# gateway_nano.net
KiCad netlist of a schematic drawn in EAGLE
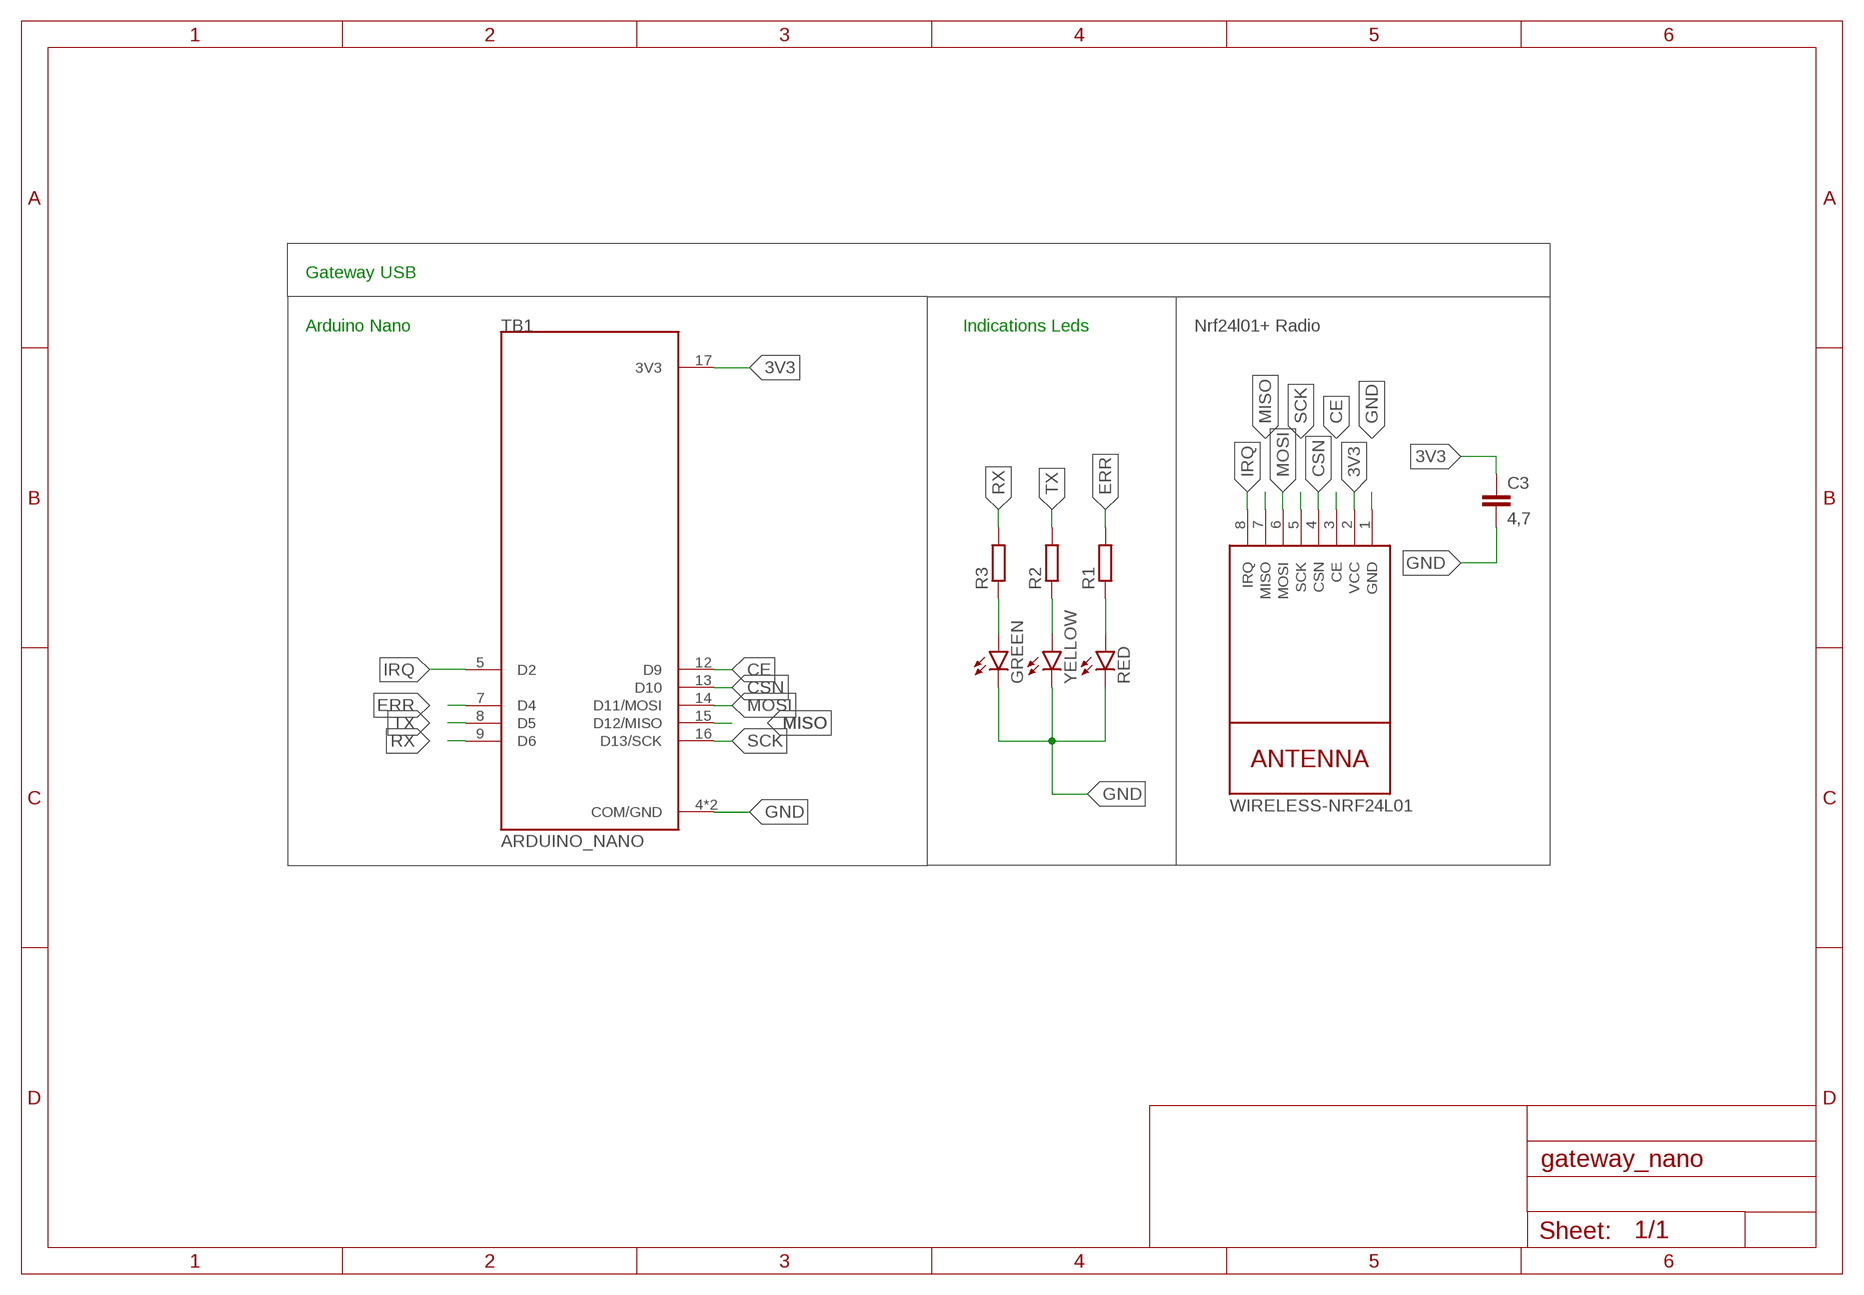
[diagram p0: schematic, sheet 1]

(export (version "E")
  (design (tool "Eeschema 10.0.6"))
  (components
    (comp (ref "C3")
      (value "4,7")
      (footprint "eagle-import:C2.5-2")
      (libsource (lib "eagle-import") (part "C2.5/2"))
    )
    (comp (ref "GREEN")
      (value "LED5MM")
      (footprint "eagle-import:LED5MM")
      (libsource (lib "eagle-import") (part "LED5MM"))
    )
    (comp (ref "NRF24L01+")
      (value "WIRELESS-NRF24L01")
      (footprint "eagle-import:WIRELESS-NRF24L01")
      (libsource (lib "eagle-import") (part "WIRELESS-NRF24L01"))
    )
    (comp (ref "R1")
      (value "R-EU_R0805")
      (footprint "eagle-import:R0805")
      (libsource (lib "eagle-import") (part "R-EU_R0805"))
    )
    (comp (ref "R2")
      (value "R-EU_R0805")
      (footprint "eagle-import:R0805")
      (libsource (lib "eagle-import") (part "R-EU_R0805"))
    )
    (comp (ref "R3")
      (value "R-EU_R0805")
      (footprint "eagle-import:R0805")
      (libsource (lib "eagle-import") (part "R-EU_R0805"))
    )
    (comp (ref "RED")
      (value "LED5MM")
      (footprint "eagle-import:LED5MM")
      (libsource (lib "eagle-import") (part "LED5MM"))
    )
    (comp (ref "TB1")
      (value "ARDUINO_NANO")
      (footprint "eagle-import:SHIELD_ARDUINO_NANO")
      (fields (field (name "MF") "Arduino") (field (name "MP") "ARDUINO NANO"))
      (libsource (lib "eagle-import") (part "ARDUINO_NANO"))
    )
    (comp (ref "YELLOW")
      (value "LED5MM")
      (footprint "eagle-import:LED5MM")
      (libsource (lib "eagle-import") (part "LED5MM"))
    )
  )
  (nets
    (net (code "1") (name "3V3") (class "Default")
      (node (ref "C3") (pin "1") (pinfunction "1_1") (pintype "passive"))
      (node (ref "NRF24L01+") (pin "2") (pinfunction "VCC_2") (pintype "power_in"))
      (node (ref "TB1") (pin "17") (pinfunction "3V3_17") (pintype "power_in"))
    )
    (net (code "2") (name "CE") (class "Default")
      (node (ref "NRF24L01+") (pin "3") (pinfunction "CE_3") (pintype "bidirectional"))
      (node (ref "TB1") (pin "12") (pinfunction "D9_12") (pintype "bidirectional"))
    )
    (net (code "3") (name "CSN") (class "Default")
      (node (ref "NRF24L01+") (pin "4") (pinfunction "CSN_4") (pintype "bidirectional"))
      (node (ref "TB1") (pin "13") (pinfunction "D10_13") (pintype "bidirectional"))
    )
    (net (code "4") (name "ERR") (class "Default")
      (node (ref "R1") (pin "2") (pinfunction "2_2") (pintype "passive"))
      (node (ref "TB1") (pin "7") (pinfunction "D4_7") (pintype "bidirectional"))
    )
    (net (code "5") (name "GND") (class "Default")
      (node (ref "C3") (pin "2") (pinfunction "2_2") (pintype "passive"))
      (node (ref "GREEN") (pin "K") (pinfunction "C_K") (pintype "passive"))
      (node (ref "NRF24L01+") (pin "1") (pinfunction "GND_1") (pintype "power_in"))
      (node (ref "RED") (pin "K") (pinfunction "C_K") (pintype "passive"))
      (node (ref "TB1") (pin "29") (pinfunction "COM/GND_29") (pintype "power_in"))
      (node (ref "TB1") (pin "4") (pinfunction "COM/GND_4") (pintype "power_in"))
      (node (ref "YELLOW") (pin "K") (pinfunction "C_K") (pintype "passive"))
    )
    (net (code "6") (name "IRQ") (class "Default")
      (node (ref "NRF24L01+") (pin "8") (pinfunction "IRQ_8") (pintype "bidirectional"))
      (node (ref "TB1") (pin "5") (pinfunction "D2_5") (pintype "bidirectional"))
    )
    (net (code "7") (name "MISO") (class "Default")
      (node (ref "NRF24L01+") (pin "7") (pinfunction "MISO_7") (pintype "bidirectional"))
      (node (ref "TB1") (pin "15") (pinfunction "D12/MISO_15") (pintype "bidirectional"))
    )
    (net (code "8") (name "MOSI") (class "Default")
      (node (ref "NRF24L01+") (pin "6") (pinfunction "MOSI_6") (pintype "bidirectional"))
      (node (ref "TB1") (pin "14") (pinfunction "D11/MOSI_14") (pintype "bidirectional"))
    )
    (net (code "9") (name "Net-(GREEN-PadA)") (class "Default")
      (node (ref "GREEN") (pin "A") (pinfunction "A_A") (pintype "passive"))
      (node (ref "R3") (pin "1") (pinfunction "1_1") (pintype "passive"))
    )
    (net (code "10") (name "Net-(R1-Pad1)") (class "Default")
      (node (ref "R1") (pin "1") (pinfunction "1_1") (pintype "passive"))
      (node (ref "RED") (pin "A") (pinfunction "A_A") (pintype "passive"))
    )
    (net (code "11") (name "Net-(R2-Pad1)") (class "Default")
      (node (ref "R2") (pin "1") (pinfunction "1_1") (pintype "passive"))
      (node (ref "YELLOW") (pin "A") (pinfunction "A_A") (pintype "passive"))
    )
    (net (code "12") (name "RX") (class "Default")
      (node (ref "R3") (pin "2") (pinfunction "2_2") (pintype "passive"))
      (node (ref "TB1") (pin "9") (pinfunction "D6_9") (pintype "bidirectional"))
    )
    (net (code "13") (name "SCK") (class "Default")
      (node (ref "NRF24L01+") (pin "5") (pinfunction "SCK_5") (pintype "bidirectional"))
      (node (ref "TB1") (pin "16") (pinfunction "D13/SCK_16") (pintype "bidirectional"))
    )
    (net (code "14") (name "TX") (class "Default")
      (node (ref "R2") (pin "2") (pinfunction "2_2") (pintype "passive"))
      (node (ref "TB1") (pin "8") (pinfunction "D5_8") (pintype "bidirectional"))
    )
  )
)
